# attendance_SYS.net
KiCad netlist of a schematic drawn in Altium Designer
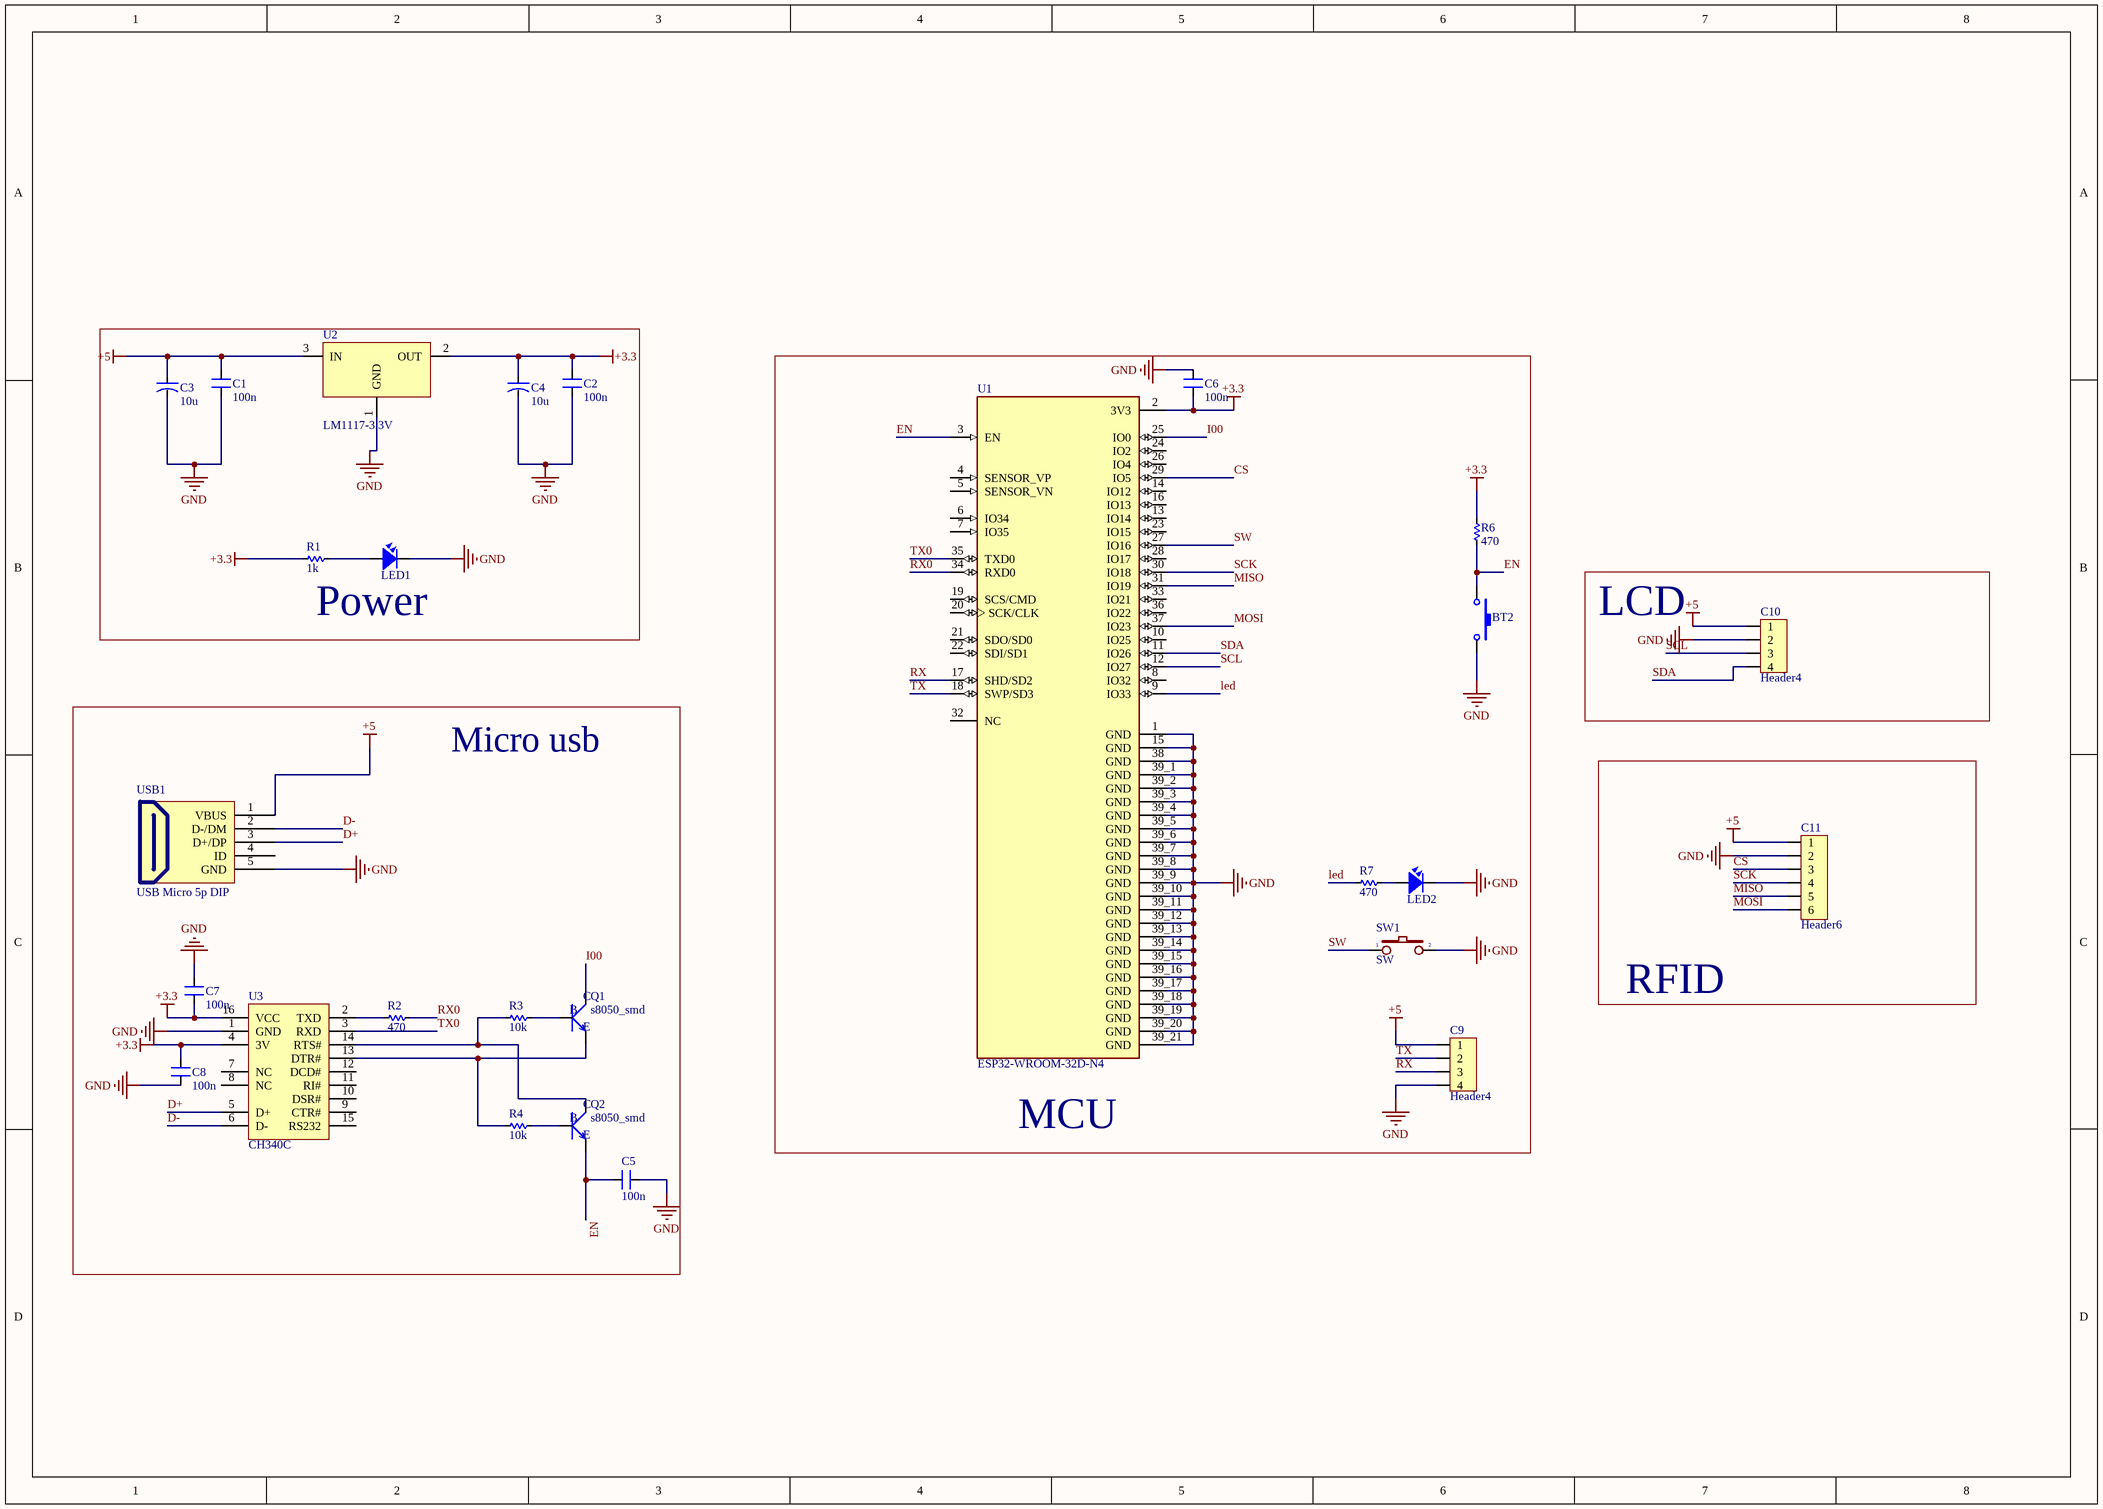
[diagram p0: attendance_SYS.SchDoc]

(export (version "E")
  (design (tool "Eeschema 10.0.6"))
  (components
    (comp (ref "BT2")
      (value "Nut Nhan 2 Chan SMD 3x6x2.5")
      (footprint "Nut Nhan 2 Chan SMD 3x6x2.5")
      (libsource (lib "Component") (part "Nut Nhan 2 Chan SMD 3x6x2.5"))
    )
    (comp (ref "C1") (value "100n") (footprint "CN-SMD-1206") (libsource (lib "Library") (part "CN")))
    (comp (ref "C2") (value "100n") (footprint "CN-SMD-1206") (libsource (lib "Library") (part "CN")))
    (comp (ref "C3")
      (value "10u")
      (footprint "CAP-ALU-SMD-5.5x5.5")
      (description "Polarized Capacitor (Axial)")
      (fields (field (name "PUBLISHER") "Altium Limited"))
      (libsource (lib "Library") (part "CN-SMD"))
    )
    (comp (ref "C4")
      (value "10u")
      (footprint "CAP-ALU-SMD-5.5x5.5")
      (description "Polarized Capacitor (Axial)")
      (fields (field (name "PUBLISHER") "Altium Limited"))
      (libsource (lib "Library") (part "CN-SMD"))
    )
    (comp (ref "C5") (value "100n") (footprint "CN-SMD-1206") (libsource (lib "Library") (part "CN")))
    (comp (ref "C6") (value "100n") (footprint "CN-SMD-1206") (libsource (lib "Library") (part "CN")))
    (comp (ref "C7") (value "100n") (footprint "CN-SMD-1206") (libsource (lib "Library") (part "CN")))
    (comp (ref "C8") (value "100n") (footprint "CN-SMD-1206") (libsource (lib "Library") (part "CN")))
    (comp (ref "C9")
      (value "Header4")
      (footprint "HDR4")
      (description "Header IDC, 4 x 1 Pin Vertical 2.54mm Pitch (Non-Boxed, Male)")
      (fields
        (field (name "MANUFACTURER") "Würth Elektronik eiSos GmbH")
        (field (name "PARTNO") "613002143121")
        (field (name "CREATED BY") "Karrer Zheng")
      )
      (libsource (lib "Library") (part "Header4"))
    )
    (comp (ref "C10")
      (value "Header4")
      (footprint "HDR4")
      (description "Header IDC, 4 x 1 Pin Vertical 2.54mm Pitch (Non-Boxed, Male)")
      (fields
        (field (name "MANUFACTURER") "Würth Elektronik eiSos GmbH")
        (field (name "PARTNO") "613002143121")
        (field (name "CREATED BY") "Karrer Zheng")
      )
      (libsource (lib "Library") (part "Header4"))
    )
    (comp (ref "C11")
      (value "Header6")
      (footprint "HDR6")
      (description "Header IDC, 6 x 1 Pin Vertical 2.54mm Pitch (Non-Boxed, Male)")
      (fields
        (field (name "MANUFACTURER") "Würth Elektronik eiSos GmbH")
        (field (name "PARTNO") "613002143121")
        (field (name "CREATED BY") "Karrer Zheng")
      )
      (libsource (lib "Library") (part "Header6"))
    )
    (comp (ref "LED1") (value "LED") (footprint "LED-1206-Red") (libsource (lib "Library") (part "LED SMD")))
    (comp (ref "LED2")
      (value "LED")
      (footprint "LED-5MM-GREEN")
      (description "LED Single colour Green and Red")
      (libsource (lib "Library") (part "LED"))
    )
    (comp (ref "Q1")
      (value "s8050_smd")
      (footprint "SOT-23")
      (description "Bipolar (BJT) Transistor NPN 25 V 500 mA 150MHz 300 mW Surface Mount SOT-23")
      (fields (field (name "MF") "UMW") (field (name "MP") "S8050"))
      (libsource (lib "Library") (part "s8050_smd"))
    )
    (comp (ref "Q2")
      (value "s8050_smd")
      (footprint "SOT-23")
      (description "Bipolar (BJT) Transistor NPN 25 V 500 mA 150MHz 300 mW Surface Mount SOT-23")
      (fields (field (name "MF") "UMW") (field (name "MP") "S8050"))
      (libsource (lib "Library") (part "s8050_smd"))
    )
    (comp (ref "R1")
      (value "1k")
      (footprint "RES-SMD-1206")
      (description "Resistor")
      (fields
        (field (name "MANUFACTURER") "Generic Components")
        (field (name "PUBLISHER") "Altium Hobart Technology Centre")
      )
      (libsource (lib "Library") (part "Res-SMD"))
    )
    (comp (ref "R2")
      (value "470")
      (footprint "RES-SMD-1206")
      (description "Resistor")
      (fields
        (field (name "MANUFACTURER") "Generic Components")
        (field (name "PUBLISHER") "Altium Hobart Technology Centre")
      )
      (libsource (lib "Library") (part "Res-SMD"))
    )
    (comp (ref "R3")
      (value "10k")
      (footprint "RES-SMD-1206")
      (description "Resistor")
      (fields
        (field (name "MANUFACTURER") "Generic Components")
        (field (name "PUBLISHER") "Altium Hobart Technology Centre")
      )
      (libsource (lib "Library") (part "Res-SMD"))
    )
    (comp (ref "R4")
      (value "10k")
      (footprint "RES-SMD-1206")
      (description "Resistor")
      (fields
        (field (name "MANUFACTURER") "Generic Components")
        (field (name "PUBLISHER") "Altium Hobart Technology Centre")
      )
      (libsource (lib "Library") (part "Res-SMD"))
    )
    (comp (ref "R6")
      (value "470")
      (footprint "RES-SMD-1206")
      (description "Resistor")
      (fields
        (field (name "MANUFACTURER") "Generic Components")
        (field (name "PUBLISHER") "Altium Hobart Technology Centre")
      )
      (libsource (lib "Library") (part "Res-SMD"))
    )
    (comp (ref "R7")
      (value "470")
      (footprint "RES-SMD-1206")
      (description "Resistor")
      (fields
        (field (name "MANUFACTURER") "Generic Components")
        (field (name "PUBLISHER") "Altium Hobart Technology Centre")
      )
      (libsource (lib "Library") (part "Res-SMD"))
    )
    (comp (ref "SW1")
      (value "SW")
      (footprint "SW1-DIP-12x12x8-Red")
      (description "Switch button 2 pin")
      (libsource (lib "Library") (part "SW2"))
    )
    (comp (ref "U1")
      (value "ESP32-WROOM-32D-N4")
      (footprint "MODULE_ESP32-WROOM-32D-N4")
      (fields (field (name "MF") "Espressif Systems"))
      (libsource (lib "biualtium") (part "ESP32-WROOM-32D-N4"))
    )
    (comp (ref "U2")
      (value "LM1117-3.3V")
      (footprint "SOT223")
      (description "800mA Low-Dropout Linear Regulator")
      (fields (field (name "CREATOR") "Nguyen Ba Bien"))
      (libsource (lib "Library") (part "LM1117"))
    )
    (comp (ref "U3")
      (value "CH340C")
      (footprint "SO16")
      (description "High and Low Side Driver")
      (fields (field (name "PUBLISHER") "Altium Limited"))
      (libsource (lib "Library") (part "CH340C"))
    )
    (comp (ref "USB1")
      (value "USB Micro 5p DIP")
      (footprint "USB Micro 5p DIP")
      (description "USB Type B")
      (libsource (lib "Component") (part "USB Micro 5p DIP"))
    )
  )
  (nets
    (net (code "1") (name "+3.3") (class "Default")
      (node (ref "C2") (pin "1") (pinfunction "1_1") (pintype "passive"))
      (node (ref "C4") (pin "1") (pinfunction "1_1") (pintype "passive"))
      (node (ref "C6") (pin "2") (pinfunction "2_2") (pintype "passive"))
      (node (ref "C7") (pin "2") (pinfunction "2_2") (pintype "passive"))
      (node (ref "C8") (pin "1") (pinfunction "1_1") (pintype "passive"))
      (node (ref "R1") (pin "2") (pinfunction "2_2") (pintype "passive"))
      (node (ref "R6") (pin "2") (pinfunction "2_2") (pintype "passive"))
      (node (ref "U1") (pin "2") (pinfunction "3V3_2") (pintype "power_in"))
      (node (ref "U2") (pin "2") (pinfunction "OUT_2") (pintype "passive"))
      (node (ref "U3") (pin "16") (pinfunction "VCC_16") (pintype "passive"))
      (node (ref "U3") (pin "4") (pinfunction "3V_4") (pintype "passive"))
    )
    (net (code "2") (name "+5") (class "Default")
      (node (ref "C1") (pin "1") (pinfunction "1_1") (pintype "passive"))
      (node (ref "C10") (pin "1") (pinfunction "1_1") (pintype "passive"))
      (node (ref "C11") (pin "1") (pinfunction "1_1") (pintype "passive"))
      (node (ref "C3") (pin "1") (pinfunction "1_1") (pintype "passive"))
      (node (ref "C9") (pin "1") (pinfunction "1_1") (pintype "passive"))
      (node (ref "U2") (pin "3") (pinfunction "IN_3") (pintype "passive"))
      (node (ref "USB1") (pin "1") (pinfunction "VBUS_1") (pintype "passive"))
    )
    (net (code "3") (name "/CS") (class "Default")
      (node (ref "C11") (pin "3") (pinfunction "3_3") (pintype "passive"))
      (node (ref "U1") (pin "29") (pinfunction "IO5_29") (pintype "bidirectional"))
    )
    (net (code "4") (name "/D+") (class "Default")
      (node (ref "U3") (pin "5") (pinfunction "D+_5") (pintype "passive"))
      (node (ref "USB1") (pin "3") (pinfunction "D+/DP_3") (pintype "passive"))
    )
    (net (code "5") (name "/D-") (class "Default")
      (node (ref "U3") (pin "6") (pinfunction "D-_6") (pintype "passive"))
      (node (ref "USB1") (pin "2") (pinfunction "D-/DM_2") (pintype "passive"))
    )
    (net (code "6") (name "/EN") (class "Default")
      (node (ref "BT2") (pin "1") (pinfunction "1_1") (pintype "passive"))
      (node (ref "C5") (pin "1") (pinfunction "1_1") (pintype "passive"))
      (node (ref "Q2") (pin "2") (pinfunction "E_2") (pintype "passive"))
      (node (ref "R6") (pin "1") (pinfunction "1_1") (pintype "passive"))
      (node (ref "U1") (pin "3") (pinfunction "EN_3") (pintype "input"))
    )
    (net (code "7") (name "/I00") (class "Default")
      (node (ref "Q1") (pin "3") (pinfunction "C_3") (pintype "passive"))
      (node (ref "U1") (pin "25") (pinfunction "IO0_25") (pintype "bidirectional"))
    )
    (net (code "8") (name "/MISO") (class "Default")
      (node (ref "C11") (pin "5") (pinfunction "5_5") (pintype "passive"))
      (node (ref "U1") (pin "31") (pinfunction "IO19_31") (pintype "bidirectional"))
    )
    (net (code "9") (name "/MOSI") (class "Default")
      (node (ref "C11") (pin "6") (pinfunction "6_6") (pintype "passive"))
      (node (ref "U1") (pin "37") (pinfunction "IO23_37") (pintype "bidirectional"))
    )
    (net (code "10") (name "/RX") (class "Default")
      (node (ref "C9") (pin "3") (pinfunction "3_3") (pintype "passive"))
      (node (ref "U1") (pin "17") (pinfunction "SHD/SD2_17") (pintype "bidirectional"))
    )
    (net (code "11") (name "/RX0") (class "Default")
      (node (ref "R2") (pin "1") (pinfunction "1_1") (pintype "passive"))
      (node (ref "U1") (pin "34") (pinfunction "RXD0_34") (pintype "bidirectional"))
    )
    (net (code "12") (name "/SCK") (class "Default")
      (node (ref "C11") (pin "4") (pinfunction "4_4") (pintype "passive"))
      (node (ref "U1") (pin "30") (pinfunction "IO18_30") (pintype "bidirectional"))
    )
    (net (code "13") (name "/SCL") (class "Default")
      (node (ref "C10") (pin "3") (pinfunction "3_3") (pintype "passive"))
      (node (ref "U1") (pin "12") (pinfunction "IO27_12") (pintype "bidirectional"))
    )
    (net (code "14") (name "/SDA") (class "Default")
      (node (ref "C10") (pin "4") (pinfunction "4_4") (pintype "passive"))
      (node (ref "U1") (pin "11") (pinfunction "IO26_11") (pintype "bidirectional"))
    )
    (net (code "15") (name "/SW") (class "Default")
      (node (ref "SW1") (pin "1") (pinfunction "1_1") (pintype "passive"))
      (node (ref "U1") (pin "27") (pinfunction "IO16_27") (pintype "bidirectional"))
    )
    (net (code "16") (name "/TX") (class "Default")
      (node (ref "C9") (pin "2") (pinfunction "2_2") (pintype "passive"))
      (node (ref "U1") (pin "18") (pinfunction "SWP/SD3_18") (pintype "bidirectional"))
    )
    (net (code "17") (name "/TX0") (class "Default")
      (node (ref "U1") (pin "35") (pinfunction "TXD0_35") (pintype "bidirectional"))
      (node (ref "U3") (pin "3") (pinfunction "RXD_3") (pintype "passive"))
    )
    (net (code "18") (name "/led") (class "Default")
      (node (ref "R7") (pin "2") (pinfunction "2_2") (pintype "passive"))
      (node (ref "U1") (pin "9") (pinfunction "IO33_9") (pintype "bidirectional"))
    )
    (net (code "19") (name "GND") (class "Default")
      (node (ref "BT2") (pin "2") (pinfunction "2_2") (pintype "passive"))
      (node (ref "C1") (pin "2") (pinfunction "2_2") (pintype "passive"))
      (node (ref "C10") (pin "2") (pinfunction "2_2") (pintype "passive"))
      (node (ref "C11") (pin "2") (pinfunction "2_2") (pintype "passive"))
      (node (ref "C2") (pin "2") (pinfunction "2_2") (pintype "passive"))
      (node (ref "C3") (pin "2") (pinfunction "2_2") (pintype "passive"))
      (node (ref "C4") (pin "2") (pinfunction "2_2") (pintype "passive"))
      (node (ref "C5") (pin "2") (pinfunction "2_2") (pintype "passive"))
      (node (ref "C6") (pin "1") (pinfunction "1_1") (pintype "passive"))
      (node (ref "C7") (pin "1") (pinfunction "1_1") (pintype "passive"))
      (node (ref "C8") (pin "2") (pinfunction "2_2") (pintype "passive"))
      (node (ref "C9") (pin "4") (pinfunction "4_4") (pintype "passive"))
      (node (ref "LED1") (pin "2") (pinfunction "2_2") (pintype "passive"))
      (node (ref "LED2") (pin "2") (pinfunction "2_2") (pintype "passive"))
      (node (ref "SW1") (pin "2") (pinfunction "2_2") (pintype "passive"))
      (node (ref "U1") (pin "1") (pinfunction "GND_1") (pintype "power_in"))
      (node (ref "U1") (pin "15") (pinfunction "GND_15") (pintype "power_in"))
      (node (ref "U1") (pin "38") (pinfunction "GND_38") (pintype "power_in"))
      (node (ref "U1") (pin "39_1") (pinfunction "GND_39_1") (pintype "power_in"))
      (node (ref "U1") (pin "39_10") (pinfunction "GND_39_10") (pintype "power_in"))
      (node (ref "U1") (pin "39_11") (pinfunction "GND_39_11") (pintype "power_in"))
      (node (ref "U1") (pin "39_12") (pinfunction "GND_39_12") (pintype "power_in"))
      (node (ref "U1") (pin "39_13") (pinfunction "GND_39_13") (pintype "power_in"))
      (node (ref "U1") (pin "39_14") (pinfunction "GND_39_14") (pintype "power_in"))
      (node (ref "U1") (pin "39_15") (pinfunction "GND_39_15") (pintype "power_in"))
      (node (ref "U1") (pin "39_16") (pinfunction "GND_39_16") (pintype "power_in"))
      (node (ref "U1") (pin "39_17") (pinfunction "GND_39_17") (pintype "power_in"))
      (node (ref "U1") (pin "39_18") (pinfunction "GND_39_18") (pintype "power_in"))
      (node (ref "U1") (pin "39_19") (pinfunction "GND_39_19") (pintype "power_in"))
      (node (ref "U1") (pin "39_2") (pinfunction "GND_39_2") (pintype "power_in"))
      (node (ref "U1") (pin "39_20") (pinfunction "GND_39_20") (pintype "power_in"))
      (node (ref "U1") (pin "39_21") (pinfunction "GND_39_21") (pintype "power_in"))
      (node (ref "U1") (pin "39_3") (pinfunction "GND_39_3") (pintype "power_in"))
      (node (ref "U1") (pin "39_4") (pinfunction "GND_39_4") (pintype "power_in"))
      (node (ref "U1") (pin "39_5") (pinfunction "GND_39_5") (pintype "power_in"))
      (node (ref "U1") (pin "39_6") (pinfunction "GND_39_6") (pintype "power_in"))
      (node (ref "U1") (pin "39_7") (pinfunction "GND_39_7") (pintype "power_in"))
      (node (ref "U1") (pin "39_8") (pinfunction "GND_39_8") (pintype "power_in"))
      (node (ref "U1") (pin "39_9") (pinfunction "GND_39_9") (pintype "power_in"))
      (node (ref "U2") (pin "1") (pinfunction "GND_1") (pintype "passive"))
      (node (ref "U3") (pin "1") (pinfunction "GND_1") (pintype "passive"))
      (node (ref "USB1") (pin "5") (pinfunction "GND_5") (pintype "passive"))
    )
    (net (code "20") (name "Net-(LED1-Pad1)") (class "Default")
      (node (ref "LED1") (pin "1") (pinfunction "1_1") (pintype "passive"))
      (node (ref "R1") (pin "1") (pinfunction "1_1") (pintype "passive"))
    )
    (net (code "21") (name "Net-(LED2-Pad1)") (class "Default")
      (node (ref "LED2") (pin "1") (pinfunction "1_1") (pintype "passive"))
      (node (ref "R7") (pin "1") (pinfunction "1_1") (pintype "passive"))
    )
    (net (code "22") (name "Net-(Q1-B)") (class "Default")
      (node (ref "Q1") (pin "1") (pinfunction "B_1") (pintype "passive"))
      (node (ref "R3") (pin "1") (pinfunction "1_1") (pintype "passive"))
    )
    (net (code "23") (name "Net-(Q1-E)") (class "Default")
      (node (ref "Q1") (pin "2") (pinfunction "E_2") (pintype "passive"))
      (node (ref "R4") (pin "2") (pinfunction "2_2") (pintype "passive"))
      (node (ref "U3") (pin "13") (pinfunction "DTR#_13") (pintype "passive"))
    )
    (net (code "24") (name "Net-(Q2-B)") (class "Default")
      (node (ref "Q2") (pin "1") (pinfunction "B_1") (pintype "passive"))
      (node (ref "R4") (pin "1") (pinfunction "1_1") (pintype "passive"))
    )
    (net (code "25") (name "Net-(Q2-C)") (class "Default")
      (node (ref "Q2") (pin "3") (pinfunction "C_3") (pintype "passive"))
      (node (ref "R3") (pin "2") (pinfunction "2_2") (pintype "passive"))
      (node (ref "U3") (pin "14") (pinfunction "RTS#_14") (pintype "passive"))
    )
    (net (code "26") (name "Net-(U3-TXD)") (class "Default")
      (node (ref "R2") (pin "2") (pinfunction "2_2") (pintype "passive"))
      (node (ref "U3") (pin "2") (pinfunction "TXD_2") (pintype "passive"))
    )
    (net (code "27") (name "unconnected-(U1-IO2-Pad24)") (class "Default")
      (node (ref "U1") (pin "24") (pinfunction "IO2_24") (pintype "bidirectional"))
    )
    (net (code "28") (name "unconnected-(U1-IO4-Pad26)") (class "Default")
      (node (ref "U1") (pin "26") (pinfunction "IO4_26") (pintype "bidirectional"))
    )
    (net (code "29") (name "unconnected-(U1-IO12-Pad14)") (class "Default")
      (node (ref "U1") (pin "14") (pinfunction "IO12_14") (pintype "bidirectional"))
    )
    (net (code "30") (name "unconnected-(U1-IO13-Pad16)") (class "Default")
      (node (ref "U1") (pin "16") (pinfunction "IO13_16") (pintype "bidirectional"))
    )
    (net (code "31") (name "unconnected-(U1-IO14-Pad13)") (class "Default")
      (node (ref "U1") (pin "13") (pinfunction "IO14_13") (pintype "bidirectional"))
    )
    (net (code "32") (name "unconnected-(U1-IO15-Pad23)") (class "Default")
      (node (ref "U1") (pin "23") (pinfunction "IO15_23") (pintype "bidirectional"))
    )
    (net (code "33") (name "unconnected-(U1-IO17-Pad28)") (class "Default")
      (node (ref "U1") (pin "28") (pinfunction "IO17_28") (pintype "bidirectional"))
    )
    (net (code "34") (name "unconnected-(U1-IO21-Pad33)") (class "Default")
      (node (ref "U1") (pin "33") (pinfunction "IO21_33") (pintype "bidirectional"))
    )
    (net (code "35") (name "unconnected-(U1-IO22-Pad36)") (class "Default")
      (node (ref "U1") (pin "36") (pinfunction "IO22_36") (pintype "bidirectional"))
    )
    (net (code "36") (name "unconnected-(U1-IO25-Pad10)") (class "Default")
      (node (ref "U1") (pin "10") (pinfunction "IO25_10") (pintype "bidirectional"))
    )
    (net (code "37") (name "unconnected-(U1-IO32-Pad8)") (class "Default")
      (node (ref "U1") (pin "8") (pinfunction "IO32_8") (pintype "bidirectional"))
    )
    (net (code "38") (name "unconnected-(U1-IO34-Pad6)") (class "Default")
      (node (ref "U1") (pin "6") (pinfunction "IO34_6") (pintype "input"))
    )
    (net (code "39") (name "unconnected-(U1-IO35-Pad7)") (class "Default")
      (node (ref "U1") (pin "7") (pinfunction "IO35_7") (pintype "input"))
    )
    (net (code "40") (name "unconnected-(U1-NC-Pad32)") (class "Default")
      (node (ref "U1") (pin "32") (pinfunction "NC_32") (pintype "passive"))
    )
    (net (code "41") (name "unconnected-(U1-SCK{slash}CLK-Pad20)") (class "Default")
      (node (ref "U1") (pin "20") (pinfunction "SCK/CLK_20") (pintype "bidirectional"))
    )
    (net (code "42") (name "unconnected-(U1-SCS{slash}CMD-Pad19)") (class "Default")
      (node (ref "U1") (pin "19") (pinfunction "SCS/CMD_19") (pintype "bidirectional"))
    )
    (net (code "43") (name "unconnected-(U1-SDI{slash}SD1-Pad22)") (class "Default")
      (node (ref "U1") (pin "22") (pinfunction "SDI/SD1_22") (pintype "bidirectional"))
    )
    (net (code "44") (name "unconnected-(U1-SDO{slash}SD0-Pad21)") (class "Default")
      (node (ref "U1") (pin "21") (pinfunction "SDO/SD0_21") (pintype "bidirectional"))
    )
    (net (code "45") (name "unconnected-(U1-SENSOR_VN-Pad5)") (class "Default")
      (node (ref "U1") (pin "5") (pinfunction "SENSOR_VN_5") (pintype "input"))
    )
    (net (code "46") (name "unconnected-(U1-SENSOR_VP-Pad4)") (class "Default")
      (node (ref "U1") (pin "4") (pinfunction "SENSOR_VP_4") (pintype "input"))
    )
    (net (code "47") (name "unconnected-(U3-CTR#-Pad9)") (class "Default")
      (node (ref "U3") (pin "9") (pinfunction "CTR#_9") (pintype "passive"))
    )
    (net (code "48") (name "unconnected-(U3-DCD#-Pad12)") (class "Default")
      (node (ref "U3") (pin "12") (pinfunction "DCD#_12") (pintype "passive"))
    )
    (net (code "49") (name "unconnected-(U3-DSR#-Pad10)") (class "Default")
      (node (ref "U3") (pin "10") (pinfunction "DSR#_10") (pintype "passive"))
    )
    (net (code "50") (name "unconnected-(U3-NC-Pad7)") (class "Default")
      (node (ref "U3") (pin "7") (pinfunction "NC_7") (pintype "passive"))
    )
    (net (code "51") (name "unconnected-(U3-NC-Pad8)") (class "Default")
      (node (ref "U3") (pin "8") (pinfunction "NC_8") (pintype "passive"))
    )
    (net (code "52") (name "unconnected-(U3-RI#-Pad11)") (class "Default")
      (node (ref "U3") (pin "11") (pinfunction "RI#_11") (pintype "passive"))
    )
    (net (code "53") (name "unconnected-(U3-RS232-Pad15)") (class "Default")
      (node (ref "U3") (pin "15") (pinfunction "RS232_15") (pintype "passive"))
    )
    (net (code "54") (name "unconnected-(USB1-ID-Pad4)") (class "Default")
      (node (ref "USB1") (pin "4") (pinfunction "ID_4") (pintype "passive"))
    )
  )
)
